# Control_PCb.net
KiCad netlist of a schematic drawn in EAGLE
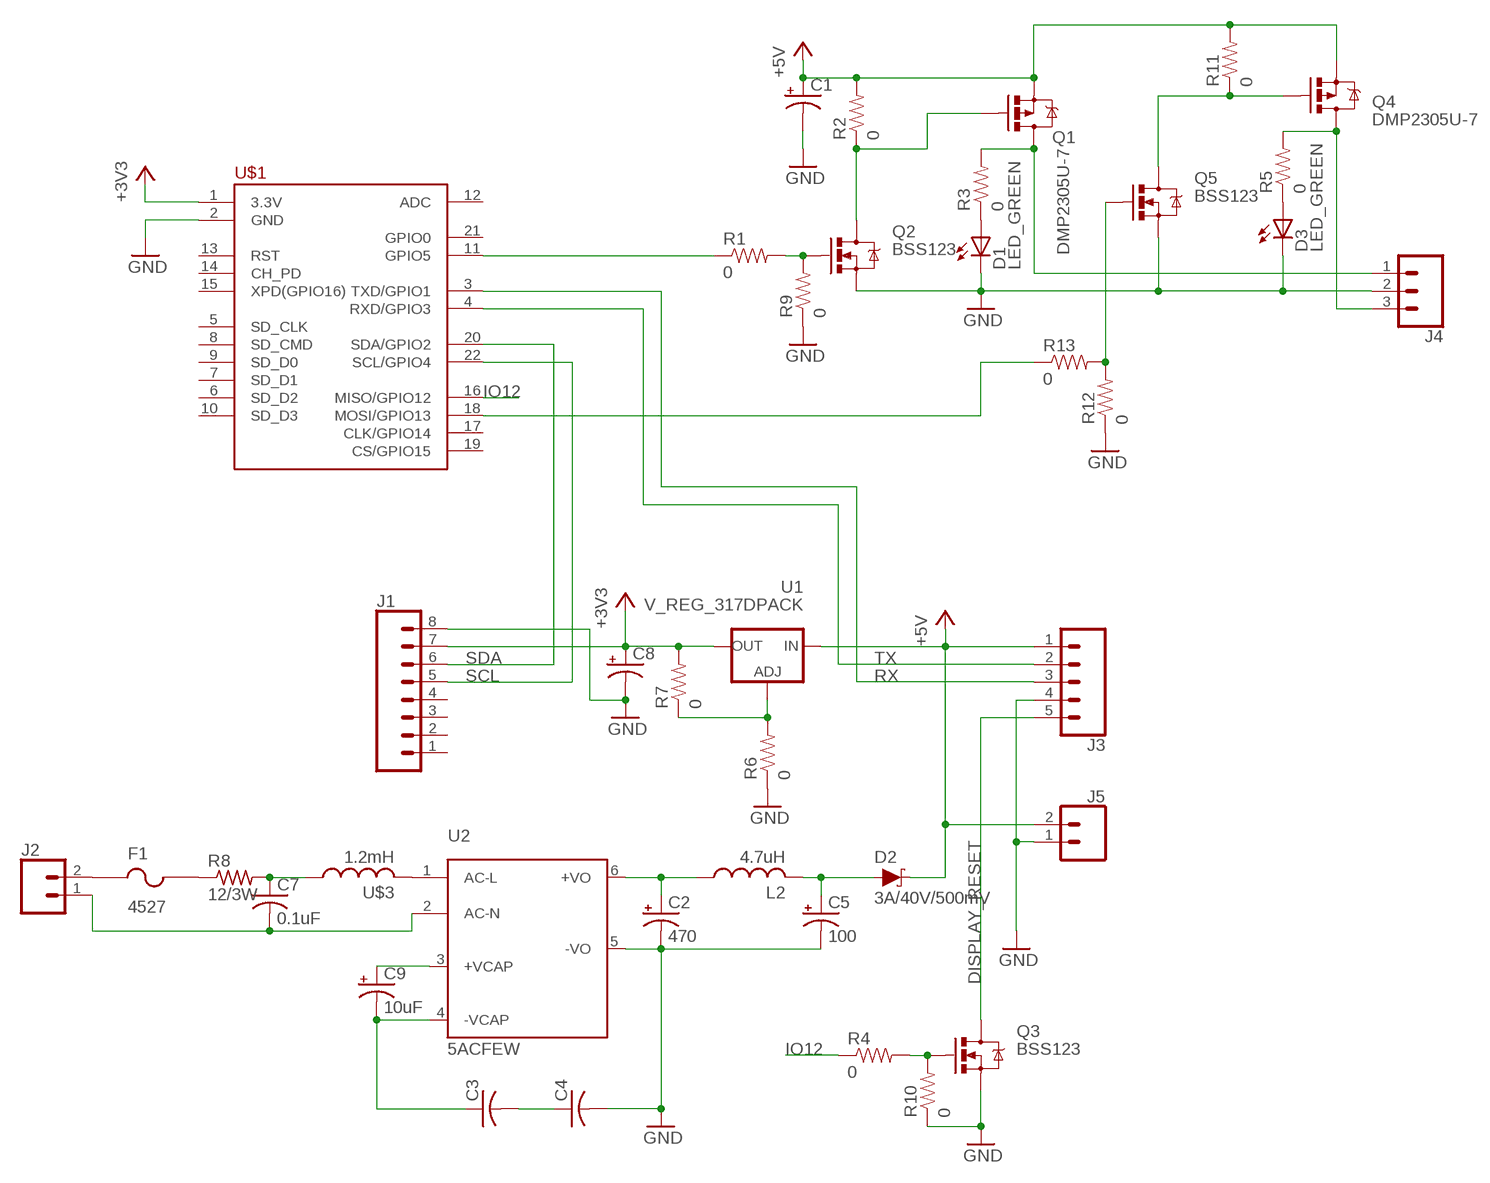
[diagram p0: schematic, sheet 1]

(export (version "E")
  (design (tool "Eeschema 10.0.6"))
  (components
    (comp (ref "C1")
      (value "CPOL-USE2,5-6E")
      (footprint "eagle-import:E2,5-6E")
      (libsource (lib "eagle-import") (part "CPOL-USE2,5-6E"))
    )
    (comp (ref "C2")
      (value "470")
      (footprint "eagle-import:CPOL-RADIAL-5MM-10MM-KIT")
      (libsource (lib "eagle-import") (part "1000UF-RADIAL-5MM-35V-20%-KIT"))
    )
    (comp (ref "C3")
      (value "C-USC1210")
      (footprint "eagle-import:C1210")
      (libsource (lib "eagle-import") (part "C-USC1210"))
    )
    (comp (ref "C4")
      (value "C-USC1210")
      (footprint "eagle-import:C1210")
      (libsource (lib "eagle-import") (part "C-USC1210"))
    )
    (comp (ref "C5")
      (value "100")
      (footprint "eagle-import:CPOL-RADIAL-5MM-10MM-KIT")
      (libsource (lib "eagle-import") (part "1000UF-RADIAL-5MM-35V-20%-KIT"))
    )
    (comp (ref "C7")
      (value "0.1uF")
      (footprint "eagle-import:C102-064X133")
      (libsource (lib "eagle-import") (part "C-US102-064X133"))
    )
    (comp (ref "C8")
      (value "CPOL-USE2,5-6E")
      (footprint "eagle-import:E2,5-6E")
      (libsource (lib "eagle-import") (part "CPOL-USE2,5-6E"))
    )
    (comp (ref "C9")
      (value "10uF")
      (footprint "eagle-import:CPOL-RADIAL-5MM-10MM-KIT")
      (libsource (lib "eagle-import") (part "1000UF-RADIAL-5MM-35V-20%-KIT"))
    )
    (comp (ref "D1")
      (value "LED_GREEN")
      (footprint "eagle-import:CHIP_LED0805")
      (fields (field (name "PARTNO") "LTST-S220GKT"))
      (libsource (lib "eagle-import") (part "LED_GREEN"))
    )
    (comp (ref "D2")
      (value "3A/40V/500mV")
      (footprint "eagle-import:SMA-DIODE")
      (libsource (lib "eagle-import") (part "DIODE-SCHOTTKY-B340A"))
    )
    (comp (ref "D3")
      (value "LED_GREEN")
      (footprint "eagle-import:CHIP_LED0805")
      (fields (field (name "PARTNO") "LTST-S220GKT"))
      (libsource (lib "eagle-import") (part "LED_GREEN"))
    )
    (comp (ref "F1")
      (value "4527")
      (footprint "eagle-import:4527")
      (libsource (lib "eagle-import") (part "4527"))
    )
    (comp (ref "J1")
      (value "CONN_08LOCK_LONGPADS")
      (footprint "eagle-import:1X08_LOCK_LONGPADS")
      (libsource (lib "eagle-import") (part "CONN_08LOCK_LONGPADS"))
    )
    (comp (ref "J2")
      (value "CONN_025MM")
      (footprint "eagle-import:SCREWTERMINAL-5MM-2")
      (libsource (lib "eagle-import") (part "CONN_025MM"))
    )
    (comp (ref "J3")
      (value "CONN_05LOCK_LONGPADS")
      (footprint "eagle-import:1X05_LOCK_LONGPADS")
      (libsource (lib "eagle-import") (part "CONN_05LOCK_LONGPADS"))
    )
    (comp (ref "J4")
      (value "CONN_03-SCREW-5MM")
      (footprint "eagle-import:SCREWTERMINAL-5MM-3")
      (libsource (lib "eagle-import") (part "CONN_03-SCREW-5MM"))
    )
    (comp (ref "J5")
      (value "CONN_025MM")
      (footprint "eagle-import:SCREWTERMINAL-5MM-2")
      (libsource (lib "eagle-import") (part "CONN_025MM"))
    )
    (comp (ref "L2")
      (value "4.7uH")
      (footprint "eagle-import:6000")
      (libsource (lib "eagle-import") (part "L"))
    )
    (comp (ref "Q1")
      (value "DMP2305U-7")
      (footprint "eagle-import:SOT23")
      (libsource (lib "eagle-import") (part "MOS-P_DMP2305U-7"))
    )
    (comp (ref "Q2")
      (value "BSS123")
      (footprint "eagle-import:SOT23")
      (fields (field (name "PARTNO") "BSS123,215"))
      (libsource (lib "eagle-import") (part "MOS-N_BSS123"))
    )
    (comp (ref "Q3")
      (value "BSS123")
      (footprint "eagle-import:SOT23")
      (fields (field (name "PARTNO") "BSS123,215"))
      (libsource (lib "eagle-import") (part "MOS-N_BSS123"))
    )
    (comp (ref "Q4")
      (value "DMP2305U-7")
      (footprint "eagle-import:SOT23")
      (libsource (lib "eagle-import") (part "MOS-P_DMP2305U-7"))
    )
    (comp (ref "Q5")
      (value "BSS123")
      (footprint "eagle-import:SOT23")
      (fields (field (name "PARTNO") "BSS123,215"))
      (libsource (lib "eagle-import") (part "MOS-N_BSS123"))
    )
    (comp (ref "R1")
      (value "0")
      (footprint "eagle-import:0805")
      (fields (field (name "PARTNO") "RC0805JR-070RL"))
      (libsource (lib "eagle-import") (part "RES_0_0805"))
    )
    (comp (ref "R2")
      (value "0")
      (footprint "eagle-import:0805")
      (fields (field (name "PARTNO") "RC0805JR-070RL"))
      (libsource (lib "eagle-import") (part "RES_0_0805"))
    )
    (comp (ref "R3")
      (value "0")
      (footprint "eagle-import:0805")
      (fields (field (name "PARTNO") "RC0805JR-070RL"))
      (libsource (lib "eagle-import") (part "RES_0_0805"))
    )
    (comp (ref "R4")
      (value "0")
      (footprint "eagle-import:0805")
      (fields (field (name "PARTNO") "RC0805JR-070RL"))
      (libsource (lib "eagle-import") (part "RES_0_0805"))
    )
    (comp (ref "R5")
      (value "0")
      (footprint "eagle-import:0805")
      (fields (field (name "PARTNO") "RC0805JR-070RL"))
      (libsource (lib "eagle-import") (part "RES_0_0805"))
    )
    (comp (ref "R6")
      (value "0")
      (footprint "eagle-import:0805")
      (fields (field (name "PARTNO") "RC0805JR-070RL"))
      (libsource (lib "eagle-import") (part "RES_0_0805"))
    )
    (comp (ref "R7")
      (value "0")
      (footprint "eagle-import:0805")
      (fields (field (name "PARTNO") "RC0805JR-070RL"))
      (libsource (lib "eagle-import") (part "RES_0_0805"))
    )
    (comp (ref "R8")
      (value "12/3W")
      (footprint "eagle-import:P0817V")
      (libsource (lib "eagle-import") (part "R-US_0817/7V"))
    )
    (comp (ref "R9")
      (value "0")
      (footprint "eagle-import:0805")
      (fields (field (name "PARTNO") "RC0805JR-070RL"))
      (libsource (lib "eagle-import") (part "RES_0_0805"))
    )
    (comp (ref "R10")
      (value "0")
      (footprint "eagle-import:0805")
      (fields (field (name "PARTNO") "RC0805JR-070RL"))
      (libsource (lib "eagle-import") (part "RES_0_0805"))
    )
    (comp (ref "R11")
      (value "0")
      (footprint "eagle-import:0805")
      (fields (field (name "PARTNO") "RC0805JR-070RL"))
      (libsource (lib "eagle-import") (part "RES_0_0805"))
    )
    (comp (ref "R12")
      (value "0")
      (footprint "eagle-import:0805")
      (fields (field (name "PARTNO") "RC0805JR-070RL"))
      (libsource (lib "eagle-import") (part "RES_0_0805"))
    )
    (comp (ref "R13")
      (value "0")
      (footprint "eagle-import:0805")
      (fields (field (name "PARTNO") "RC0805JR-070RL"))
      (libsource (lib "eagle-import") (part "RES_0_0805"))
    )
    (comp (ref "U$1")
      (value "OLIMEX_MOD-WIFI-ESP8266-DEV>PINS-INSIDE")
      (footprint "eagle-import:OLIMEX_MOD-WIFI-ESP8266-DEV-PINS-INSIDE")
      (libsource (lib "eagle-import") (part "OLIMEX_MOD-WIFI-ESP8266-DEV{gt}PINS-INSIDE"))
    )
    (comp (ref "U$3")
      (value "1.2mH")
      (footprint "eagle-import:1800R")
      (libsource (lib "eagle-import") (part "L1800R"))
    )
    (comp (ref "U1")
      (value "V_REG_317DPACK")
      (footprint "eagle-import:V-REG_DPACK")
      (libsource (lib "eagle-import") (part "V_REG_317DPACK"))
    )
    (comp (ref "U2")
      (value "5ACFEW")
      (footprint "eagle-import:5ACFEW")
      (libsource (lib "eagle-import") (part "5ACFEW"))
    )
  )
  (nets
    (net (code "1") (name "+3V3") (class "Default")
      (node (ref "C8") (pin "+") (pinfunction "+_+") (pintype "passive"))
      (node (ref "J1") (pin "7") (pinfunction "7_7") (pintype "passive"))
      (node (ref "R7") (pin "2") (pinfunction "2_2") (pintype "passive"))
      (node (ref "U$1") (pin "1") (pinfunction "3.3V_1") (pintype "power_in"))
      (node (ref "U1") (pin "4") (pinfunction "OUT_4") (pintype "output"))
    )
    (net (code "2") (name "+5V") (class "Default")
      (node (ref "C1") (pin "+") (pinfunction "+_+") (pintype "passive"))
      (node (ref "D2") (pin "C") (pinfunction "C_C") (pintype "passive"))
      (node (ref "J3") (pin "1") (pinfunction "1_1") (pintype "passive"))
      (node (ref "J5") (pin "2") (pinfunction "2_2") (pintype "passive"))
      (node (ref "Q1") (pin "3") (pinfunction "S_3") (pintype "passive"))
      (node (ref "Q4") (pin "3") (pinfunction "S_3") (pintype "passive"))
      (node (ref "R11") (pin "2") (pinfunction "2_2") (pintype "passive"))
      (node (ref "R2") (pin "2") (pinfunction "2_2") (pintype "passive"))
      (node (ref "U1") (pin "3") (pinfunction "IN_3") (pintype "input"))
    )
    (net (code "3") (name "/DISPLAY_RESET") (class "Default")
      (node (ref "J3") (pin "5") (pinfunction "5_5") (pintype "passive"))
      (node (ref "Q3") (pin "3") (pinfunction "D_3") (pintype "passive"))
    )
    (net (code "4") (name "/IO12") (class "Default")
      (node (ref "R4") (pin "1") (pinfunction "1_1") (pintype "passive"))
      (node (ref "U$1") (pin "16") (pinfunction "MISO/GPIO12_16") (pintype "bidirectional"))
    )
    (net (code "5") (name "/RX") (class "Default")
      (node (ref "J3") (pin "3") (pinfunction "3_3") (pintype "passive"))
      (node (ref "U$1") (pin "3") (pinfunction "TXD/GPIO1_3") (pintype "bidirectional"))
    )
    (net (code "6") (name "/SCL") (class "Default")
      (node (ref "J1") (pin "5") (pinfunction "5_5") (pintype "passive"))
      (node (ref "U$1") (pin "22") (pinfunction "SCL/GPIO4_22") (pintype "bidirectional"))
    )
    (net (code "7") (name "/SDA") (class "Default")
      (node (ref "J1") (pin "6") (pinfunction "6_6") (pintype "passive"))
      (node (ref "U$1") (pin "20") (pinfunction "SDA/GPIO2_20") (pintype "bidirectional"))
    )
    (net (code "8") (name "/TX") (class "Default")
      (node (ref "J3") (pin "2") (pinfunction "2_2") (pintype "passive"))
      (node (ref "U$1") (pin "4") (pinfunction "RXD/GPIO3_4") (pintype "bidirectional"))
    )
    (net (code "9") (name "GND") (class "Default")
      (node (ref "C1") (pin "-") (pinfunction "-_-") (pintype "passive"))
      (node (ref "C2") (pin "-") (pinfunction "-_-") (pintype "passive"))
      (node (ref "C4") (pin "2") (pinfunction "2_2") (pintype "passive"))
      (node (ref "C5") (pin "-") (pinfunction "-_-") (pintype "passive"))
      (node (ref "C8") (pin "-") (pinfunction "-_-") (pintype "passive"))
      (node (ref "D1") (pin "C") (pinfunction "C_C") (pintype "passive"))
      (node (ref "D3") (pin "C") (pinfunction "C_C") (pintype "passive"))
      (node (ref "J1") (pin "8") (pinfunction "8_8") (pintype "passive"))
      (node (ref "J3") (pin "4") (pinfunction "4_4") (pintype "passive"))
      (node (ref "J4") (pin "2") (pinfunction "2_2") (pintype "passive"))
      (node (ref "J5") (pin "1") (pinfunction "1_1") (pintype "passive"))
      (node (ref "Q2") (pin "2") (pinfunction "S_2") (pintype "passive"))
      (node (ref "Q3") (pin "2") (pinfunction "S_2") (pintype "passive"))
      (node (ref "Q5") (pin "2") (pinfunction "S_2") (pintype "passive"))
      (node (ref "R10") (pin "1") (pinfunction "1_1") (pintype "passive"))
      (node (ref "R12") (pin "1") (pinfunction "1_1") (pintype "passive"))
      (node (ref "R6") (pin "1") (pinfunction "1_1") (pintype "passive"))
      (node (ref "R9") (pin "1") (pinfunction "1_1") (pintype "passive"))
      (node (ref "U$1") (pin "2") (pinfunction "GND_2") (pintype "power_in"))
      (node (ref "U2") (pin "5") (pinfunction "-VO_5") (pintype "bidirectional"))
    )
    (net (code "10") (name "Net-(C3-Pad2)") (class "Default")
      (node (ref "C3") (pin "2") (pinfunction "2_2") (pintype "passive"))
      (node (ref "C4") (pin "1") (pinfunction "1_1") (pintype "passive"))
    )
    (net (code "11") (name "Net-(C5-Pad+)") (class "Default")
      (node (ref "C5") (pin "+") (pinfunction "+_+") (pintype "passive"))
      (node (ref "D2") (pin "A") (pinfunction "A_A") (pintype "passive"))
      (node (ref "L2") (pin "2") (pinfunction "2_2") (pintype "passive"))
    )
    (net (code "12") (name "Net-(C7-Pad1)") (class "Default")
      (node (ref "C7") (pin "1") (pinfunction "1_1") (pintype "passive"))
      (node (ref "R8") (pin "2") (pinfunction "2_2") (pintype "passive"))
      (node (ref "U$3") (pin "1") (pinfunction "1_1") (pintype "passive"))
    )
    (net (code "13") (name "Net-(D1-PadA)") (class "Default")
      (node (ref "D1") (pin "A") (pinfunction "A_A") (pintype "passive"))
      (node (ref "R3") (pin "1") (pinfunction "1_1") (pintype "passive"))
    )
    (net (code "14") (name "Net-(D3-PadA)") (class "Default")
      (node (ref "D3") (pin "A") (pinfunction "A_A") (pintype "passive"))
      (node (ref "R5") (pin "1") (pinfunction "1_1") (pintype "passive"))
    )
    (net (code "15") (name "Net-(F1-P$1)") (class "Default")
      (node (ref "F1") (pin "1") (pinfunction "P$1_1") (pintype "bidirectional"))
      (node (ref "J2") (pin "2") (pinfunction "2_2") (pintype "passive"))
    )
    (net (code "16") (name "Net-(F1-P$2)") (class "Default")
      (node (ref "F1") (pin "2") (pinfunction "P$2_2") (pintype "bidirectional"))
      (node (ref "R8") (pin "1") (pinfunction "1_1") (pintype "passive"))
    )
    (net (code "17") (name "Net-(Q1-D)") (class "Default")
      (node (ref "J4") (pin "1") (pinfunction "1_1") (pintype "passive"))
      (node (ref "Q1") (pin "2") (pinfunction "D_2") (pintype "passive"))
      (node (ref "R3") (pin "2") (pinfunction "2_2") (pintype "passive"))
    )
    (net (code "18") (name "Net-(Q1-G)") (class "Default")
      (node (ref "Q1") (pin "1") (pinfunction "G_1") (pintype "passive"))
      (node (ref "Q2") (pin "3") (pinfunction "D_3") (pintype "passive"))
      (node (ref "R2") (pin "1") (pinfunction "1_1") (pintype "passive"))
    )
    (net (code "19") (name "Net-(Q2-G)") (class "Default")
      (node (ref "Q2") (pin "1") (pinfunction "G_1") (pintype "passive"))
      (node (ref "R1") (pin "2") (pinfunction "2_2") (pintype "passive"))
      (node (ref "R9") (pin "2") (pinfunction "2_2") (pintype "passive"))
    )
    (net (code "20") (name "Net-(Q3-G)") (class "Default")
      (node (ref "Q3") (pin "1") (pinfunction "G_1") (pintype "passive"))
      (node (ref "R10") (pin "2") (pinfunction "2_2") (pintype "passive"))
      (node (ref "R4") (pin "2") (pinfunction "2_2") (pintype "passive"))
    )
    (net (code "21") (name "Net-(Q4-D)") (class "Default")
      (node (ref "J4") (pin "3") (pinfunction "3_3") (pintype "passive"))
      (node (ref "Q4") (pin "2") (pinfunction "D_2") (pintype "passive"))
      (node (ref "R5") (pin "2") (pinfunction "2_2") (pintype "passive"))
    )
    (net (code "22") (name "Net-(Q4-G)") (class "Default")
      (node (ref "Q4") (pin "1") (pinfunction "G_1") (pintype "passive"))
      (node (ref "Q5") (pin "3") (pinfunction "D_3") (pintype "passive"))
      (node (ref "R11") (pin "1") (pinfunction "1_1") (pintype "passive"))
    )
    (net (code "23") (name "Net-(Q5-G)") (class "Default")
      (node (ref "Q5") (pin "1") (pinfunction "G_1") (pintype "passive"))
      (node (ref "R12") (pin "2") (pinfunction "2_2") (pintype "passive"))
      (node (ref "R13") (pin "2") (pinfunction "2_2") (pintype "passive"))
    )
    (net (code "24") (name "Net-(U$1-GPIO5)") (class "Default")
      (node (ref "R1") (pin "1") (pinfunction "1_1") (pintype "passive"))
      (node (ref "U$1") (pin "11") (pinfunction "GPIO5_11") (pintype "bidirectional"))
    )
    (net (code "25") (name "Net-(U$1-MOSI{slash}GPIO13)") (class "Default")
      (node (ref "R13") (pin "1") (pinfunction "1_1") (pintype "passive"))
      (node (ref "U$1") (pin "18") (pinfunction "MOSI/GPIO13_18") (pintype "bidirectional"))
    )
    (net (code "26") (name "Net-(U1-ADJ)") (class "Default")
      (node (ref "R6") (pin "2") (pinfunction "2_2") (pintype "passive"))
      (node (ref "R7") (pin "1") (pinfunction "1_1") (pintype "passive"))
      (node (ref "U1") (pin "1") (pinfunction "ADJ_1") (pintype "input"))
    )
    (net (code "27") (name "Net-(U2-+VCAP)") (class "Default")
      (node (ref "C9") (pin "+") (pinfunction "+_+") (pintype "passive"))
      (node (ref "U2") (pin "3") (pinfunction "+VCAP_3") (pintype "bidirectional"))
    )
    (net (code "28") (name "Net-(U2-+VO)") (class "Default")
      (node (ref "C2") (pin "+") (pinfunction "+_+") (pintype "passive"))
      (node (ref "L2") (pin "1") (pinfunction "1_1") (pintype "passive"))
      (node (ref "U2") (pin "6") (pinfunction "+VO_6") (pintype "bidirectional"))
    )
    (net (code "29") (name "Net-(U2--VCAP)") (class "Default")
      (node (ref "C3") (pin "1") (pinfunction "1_1") (pintype "passive"))
      (node (ref "C9") (pin "-") (pinfunction "-_-") (pintype "passive"))
      (node (ref "U2") (pin "4") (pinfunction "-VCAP_4") (pintype "bidirectional"))
    )
    (net (code "30") (name "Net-(U2-AC-L)") (class "Default")
      (node (ref "U$3") (pin "2") (pinfunction "2_2") (pintype "passive"))
      (node (ref "U2") (pin "1") (pinfunction "AC-L_1") (pintype "bidirectional"))
    )
    (net (code "31") (name "Net-(U2-AC-N)") (class "Default")
      (node (ref "C7") (pin "2") (pinfunction "2_2") (pintype "passive"))
      (node (ref "J2") (pin "1") (pinfunction "1_1") (pintype "passive"))
      (node (ref "U2") (pin "2") (pinfunction "AC-N_2") (pintype "bidirectional"))
    )
    (net (code "32") (name "unconnected-(J1-Pad1)") (class "Default")
      (node (ref "J1") (pin "1") (pinfunction "1_1") (pintype "passive"))
    )
    (net (code "33") (name "unconnected-(J1-Pad2)") (class "Default")
      (node (ref "J1") (pin "2") (pinfunction "2_2") (pintype "passive"))
    )
    (net (code "34") (name "unconnected-(J1-Pad3)") (class "Default")
      (node (ref "J1") (pin "3") (pinfunction "3_3") (pintype "passive"))
    )
    (net (code "35") (name "unconnected-(J1-Pad4)") (class "Default")
      (node (ref "J1") (pin "4") (pinfunction "4_4") (pintype "passive"))
    )
    (net (code "36") (name "unconnected-(U$1-ADC-Pad12)") (class "Default")
      (node (ref "U$1") (pin "12") (pinfunction "ADC_12") (pintype "bidirectional"))
    )
    (net (code "37") (name "unconnected-(U$1-CH_PD-Pad14)") (class "Default")
      (node (ref "U$1") (pin "14") (pinfunction "CH_PD_14") (pintype "input"))
    )
    (net (code "38") (name "unconnected-(U$1-CLK{slash}GPIO14-Pad17)") (class "Default")
      (node (ref "U$1") (pin "17") (pinfunction "CLK/GPIO14_17") (pintype "bidirectional"))
    )
    (net (code "39") (name "unconnected-(U$1-CS{slash}GPIO15-Pad19)") (class "Default")
      (node (ref "U$1") (pin "19") (pinfunction "CS/GPIO15_19") (pintype "bidirectional"))
    )
    (net (code "40") (name "unconnected-(U$1-GPIO0-Pad21)") (class "Default")
      (node (ref "U$1") (pin "21") (pinfunction "GPIO0_21") (pintype "bidirectional"))
    )
    (net (code "41") (name "unconnected-(U$1-RST-Pad13)") (class "Default")
      (node (ref "U$1") (pin "13") (pinfunction "RST_13") (pintype "input"))
    )
    (net (code "42") (name "unconnected-(U$1-SD_CLK-Pad5)") (class "Default")
      (node (ref "U$1") (pin "5") (pinfunction "SD_CLK_5") (pintype "bidirectional"))
    )
    (net (code "43") (name "unconnected-(U$1-SD_CMD-Pad8)") (class "Default")
      (node (ref "U$1") (pin "8") (pinfunction "SD_CMD_8") (pintype "bidirectional"))
    )
    (net (code "44") (name "unconnected-(U$1-SD_D0-Pad9)") (class "Default")
      (node (ref "U$1") (pin "9") (pinfunction "SD_D0_9") (pintype "bidirectional"))
    )
    (net (code "45") (name "unconnected-(U$1-SD_D1-Pad7)") (class "Default")
      (node (ref "U$1") (pin "7") (pinfunction "SD_D1_7") (pintype "bidirectional"))
    )
    (net (code "46") (name "unconnected-(U$1-SD_D2-Pad6)") (class "Default")
      (node (ref "U$1") (pin "6") (pinfunction "SD_D2_6") (pintype "bidirectional"))
    )
    (net (code "47") (name "unconnected-(U$1-SD_D3-Pad10)") (class "Default")
      (node (ref "U$1") (pin "10") (pinfunction "SD_D3_10") (pintype "bidirectional"))
    )
    (net (code "48") (name "unconnected-(U$1-XPD(GPIO16)-Pad15)") (class "Default")
      (node (ref "U$1") (pin "15") (pinfunction "XPD(GPIO16)_15") (pintype "bidirectional"))
    )
  )
)
